# soc.net
KiCad netlist of a schematic drawn in Altium Designer
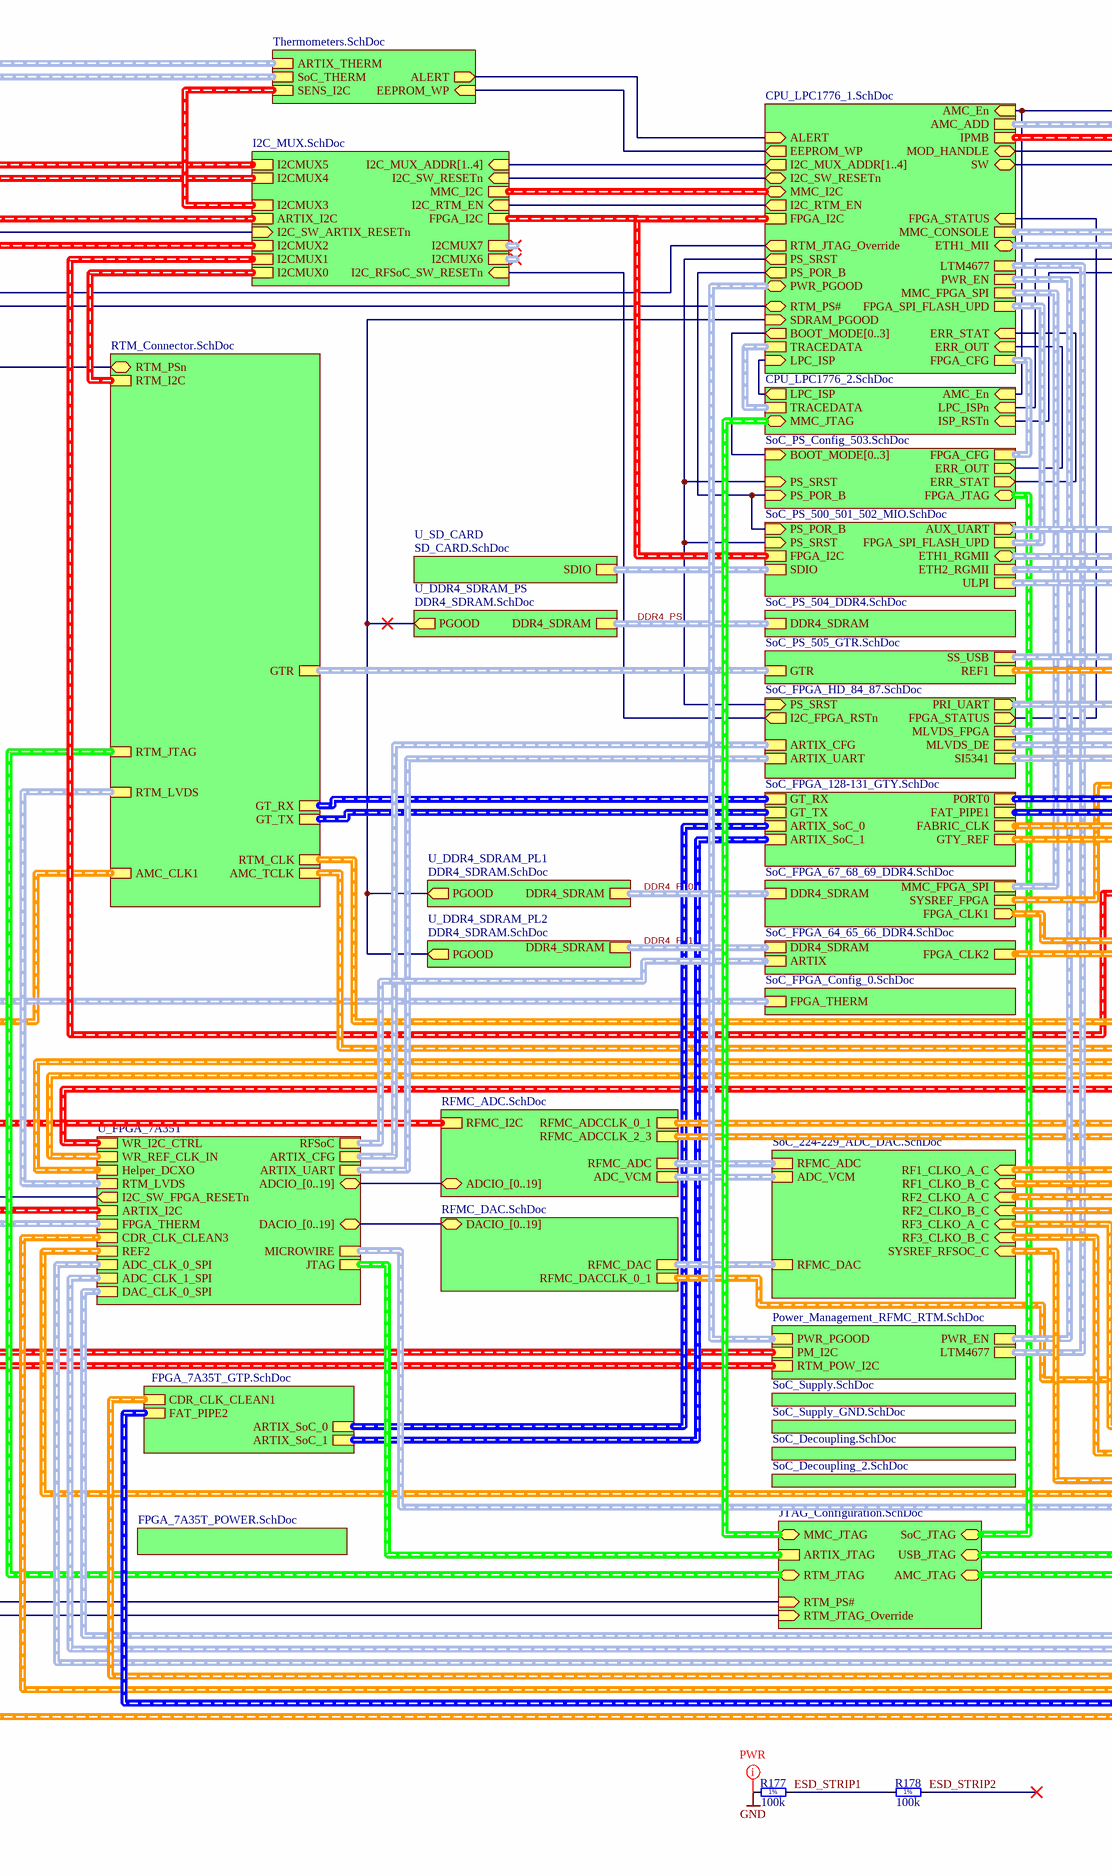
[diagram p0: soc.SchDoc, left]
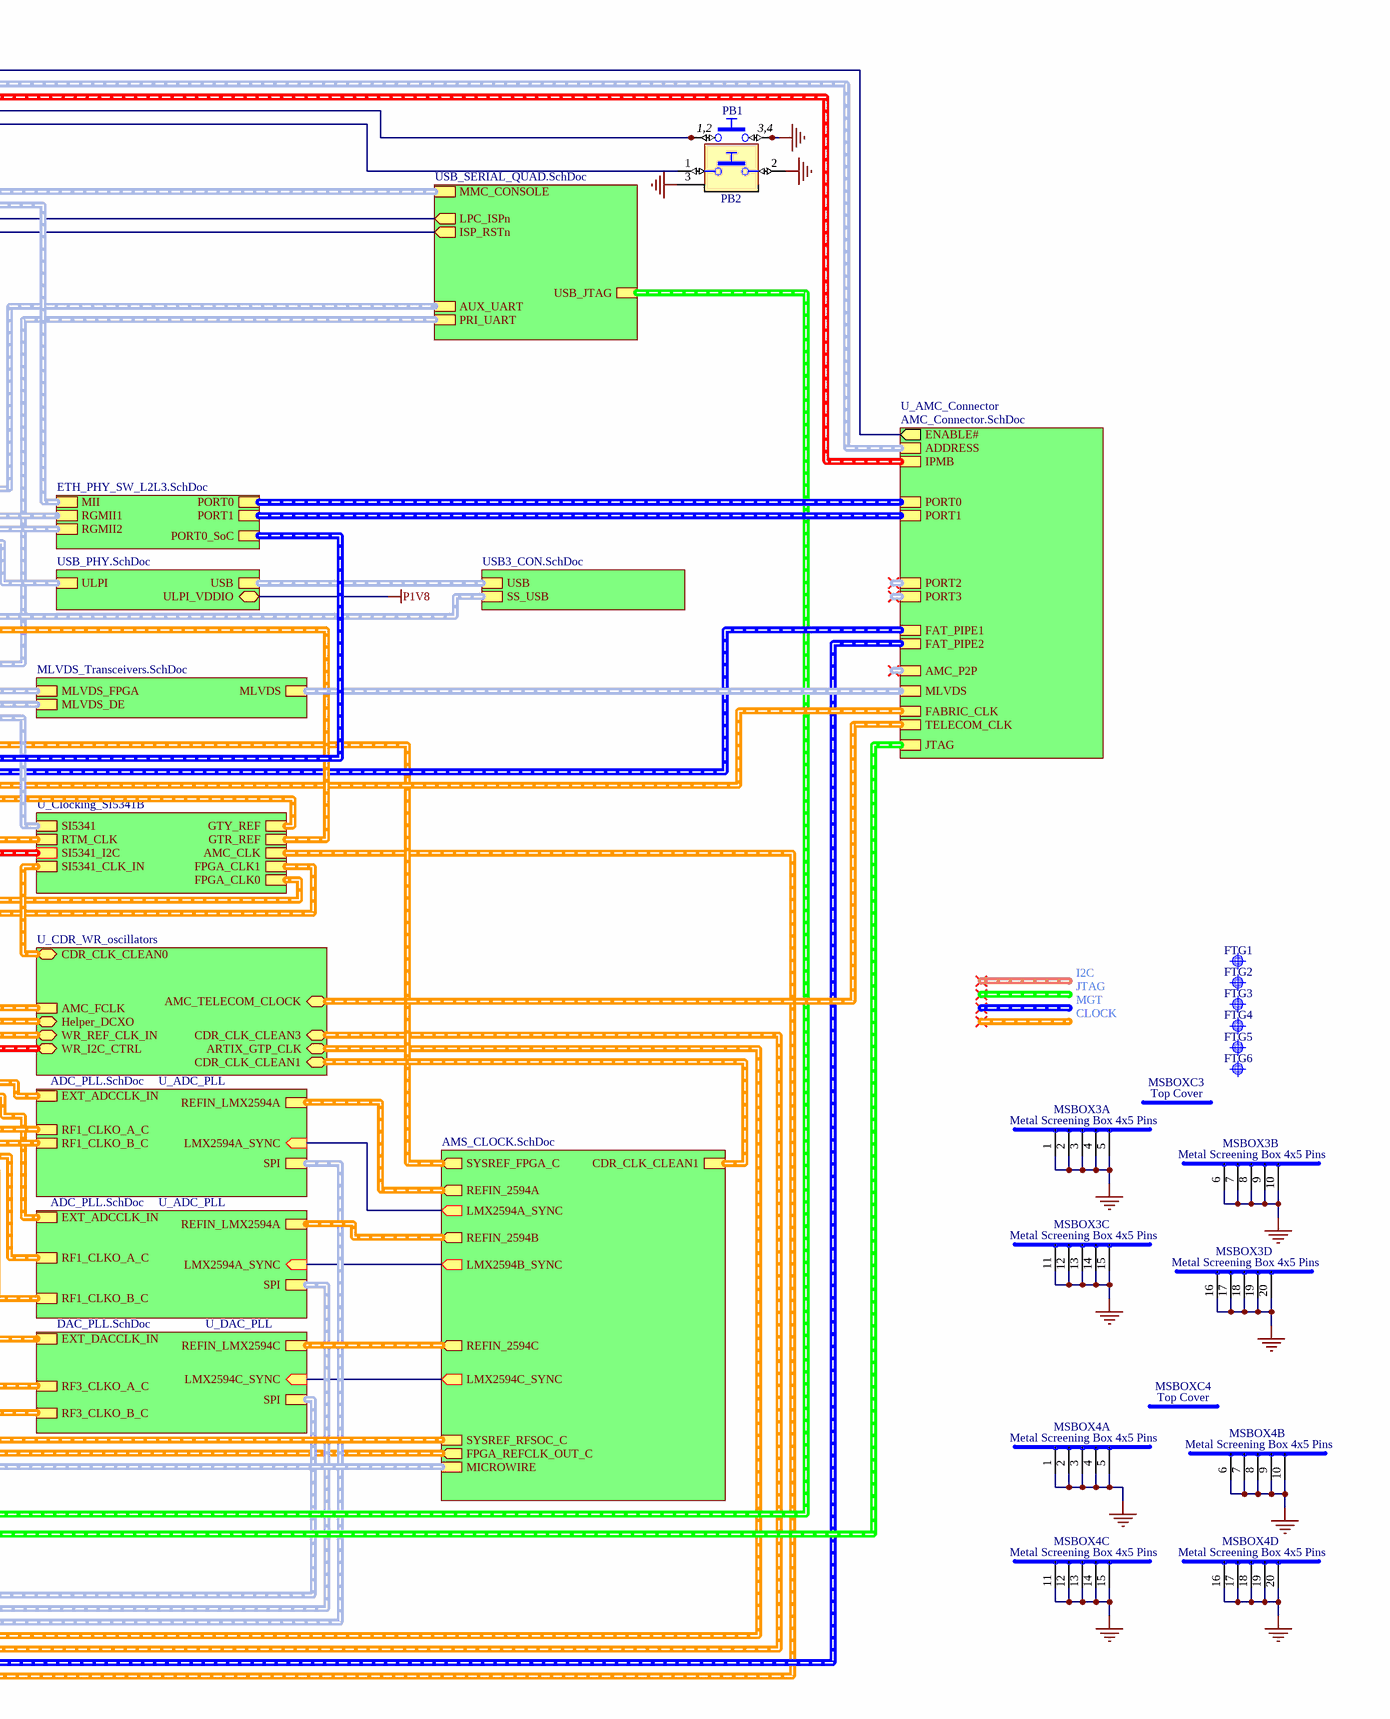
[diagram p1: soc.SchDoc, right]

(export (version "E")
  (design (tool "Eeschema 10.0.6"))
  (components
    (comp (ref "FTG1")
      (value "Use only in PCB")
      (footprint "FIDUCIAL_TOP_C100-200")
      (description "Fiducial Target")
      (fields (field (name "PART NUMBER") "FIDUCIAL_TARGET_C100-200") (field (name "AUTHOR") "CERN DEM JLC"))
      (libsource (lib "Eletro-mechanical") (part "Fiducial Target"))
    )
    (comp (ref "FTG2")
      (value "Use only in PCB")
      (footprint "FIDUCIAL_TOP_C100-200")
      (description "Fiducial Target")
      (fields (field (name "PART NUMBER") "FIDUCIAL_TARGET_C100-200") (field (name "AUTHOR") "CERN DEM JLC"))
      (libsource (lib "Eletro-mechanical") (part "Fiducial Target"))
    )
    (comp (ref "FTG3")
      (value "Use only in PCB")
      (footprint "FIDUCIAL_TOP_S200-400")
      (description "Fiducial Target")
      (fields (field (name "PART NUMBER") "FIDUCIAL_TARGET_S200-400") (field (name "AUTHOR") "CERN DEM JLC"))
      (libsource (lib "Eletro-mechanical") (part "Fiducial Target"))
    )
    (comp (ref "FTG4")
      (value "Use only in PCB")
      (footprint "FIDUCIAL_TOP_C100-200")
      (description "Fiducial Target")
      (fields (field (name "PART NUMBER") "FIDUCIAL_TARGET_C100-200") (field (name "AUTHOR") "CERN DEM JLC"))
      (libsource (lib "Eletro-mechanical") (part "Fiducial Target"))
    )
    (comp (ref "FTG5")
      (value "Use only in PCB")
      (footprint "FIDUCIAL_TOP_C100-200")
      (description "Fiducial Target")
      (fields (field (name "PART NUMBER") "FIDUCIAL_TARGET_C100-200") (field (name "AUTHOR") "CERN DEM JLC"))
      (libsource (lib "Eletro-mechanical") (part "Fiducial Target"))
    )
    (comp (ref "FTG6")
      (value "Use only in PCB")
      (footprint "FIDUCIAL_TOP_S200-400")
      (description "Fiducial Target")
      (fields (field (name "PART NUMBER") "FIDUCIAL_TARGET_S200-400") (field (name "AUTHOR") "CERN DEM JLC"))
      (libsource (lib "Eletro-mechanical") (part "Fiducial Target"))
    )
    (comp (ref "MSBOX3")
      (value "Metal Screening Box 4x5 Pins")
      (footprint "MSBOX_WURTH_36103305")
      (description "Metal Screening Box 20 (4x5) Pins")
      (fields
        (field (name "PART NUMBER") "MSBOX_WURTH_36103305")
        (field (name "MANUFACTURER") "WURTH")
        (field (name "AUTHOR") "CERN DEM JLC")
      )
      (libsource (lib "Eletro-mechanical") (part "Metal Screening Box - 4x5 pins"))
    )
    (comp (ref "MSBOX4")
      (value "Metal Screening Box 4x5 Pins")
      (footprint "MSBOX_WURTH_36103305")
      (description "Metal Screening Box 20 (4x5) Pins")
      (fields
        (field (name "PART NUMBER") "MSBOX_WURTH_36103305")
        (field (name "MANUFACTURER") "WURTH")
        (field (name "AUTHOR") "CERN DEM JLC")
      )
      (libsource (lib "Eletro-mechanical") (part "Metal Screening Box - 4x5 pins"))
    )
    (comp (ref "MSBOXC3")
      (value "Top Cover")
      (footprint "MSBOX_WURTH_36003300")
      (description "Metal Screening Box - Top Cover 0 Pin")
      (fields
        (field (name "PART NUMBER") "MSBOX_WURTH_36003300")
        (field (name "MANUFACTURER") "WURTH")
        (field (name "AUTHOR") "CERN DEM JLC")
      )
      (libsource (lib "Eletro-mechanical") (part "Metal Screening Box - Top Cover"))
    )
    (comp (ref "MSBOXC4")
      (value "Top Cover")
      (footprint "MSBOX_WURTH_36003300")
      (description "Metal Screening Box - Top Cover 0 Pin")
      (fields
        (field (name "PART NUMBER") "MSBOX_WURTH_36003300")
        (field (name "MANUFACTURER") "WURTH")
        (field (name "AUTHOR") "CERN DEM JLC")
      )
      (libsource (lib "Eletro-mechanical") (part "Metal Screening Box - Top Cover"))
    )
    (comp (ref "PB1")
      (value "Push Button")
      (footprint "SW_C&K_HDT0001")
      (description "Push-Button Switch SPDT")
      (fields
        (field (name "MANUFACTURER PART NUMBER") "HDT0001")
        (field (name "MANUFACTURER") "C&K")
        (field (name "AUTHOR") "CERN DEM JLC")
      )
      (libsource (lib "Eletro-mechanical") (part "PB SPST 12NO-34NO"))
    )
    (comp (ref "PB2")
      (value "Push Button")
      (footprint "PB_OMRON_B3U-1100P")
      (description "Push-Button Switch SPDT")
      (fields
        (field (name "PART NUMBER") "PB_OMRON_B3U-1100P")
        (field (name "MANUFACTURER") "OMRON")
        (field (name "AUTHOR") "CERN DEM JLC")
      )
      (libsource (lib "Eletro-mechanical") (part "PB SPST 1NO-2NO 3CASE"))
    )
    (comp (ref "R177")
      (value "100k")
      (footprint "RESC3216X65N")
      (description "Resistor - 1%")
      (fields
        (field (name "PART NUMBER") "R1206_100K_1%_0.25W_100PPM")
        (field (name "POWER") "0.25W")
        (field (name "AUTHOR") "CERN DEM JLC")
      )
      (libsource (lib "Resistors") (part "Resistor - 1%"))
    )
    (comp (ref "R178")
      (value "100k")
      (footprint "RESC3216X65N")
      (description "Resistor - 1%")
      (fields
        (field (name "PART NUMBER") "R1206_100K_1%_0.25W_100PPM")
        (field (name "POWER") "0.25W")
        (field (name "AUTHOR") "CERN DEM JLC")
      )
      (libsource (lib "Resistors") (part "Resistor - 1%"))
    )
  )
  (nets
    (net (code "35") (name "/ESD_STRIP1") (class "Default")
      (node (ref "R177") (pin "2") (pinfunction "2_2") (pintype "passive"))
      (node (ref "R178") (pin "1") (pinfunction "1_1") (pintype "passive"))
    )
    (net (code "36") (name "/ESD_STRIP2") (class "Default")
      (node (ref "R178") (pin "2") (pinfunction "2_2") (pintype "passive+no_connect"))
    )
    (net (code "90") (name "/MOD_HANDLE") (class "Default")
      (node (ref "PB1") (pin "1") (pinfunction "1_1") (pintype "bidirectional"))
      (node (ref "PB1") (pin "2") (pinfunction "2_2") (pintype "bidirectional"))
    )
    (net (code "121") (name "/SW") (class "Default")
      (node (ref "PB2") (pin "1") (pinfunction "1_1") (pintype "bidirectional"))
    )
    (net (code "133") (name "GND") (class "Default")
      (node (ref "MSBOX3") (pin "1") (pinfunction "1_1") (pintype "passive"))
      (node (ref "MSBOX3") (pin "10") (pinfunction "10_10") (pintype "passive"))
      (node (ref "MSBOX3") (pin "11") (pinfunction "11_11") (pintype "passive"))
      (node (ref "MSBOX3") (pin "12") (pinfunction "12_12") (pintype "passive"))
      (node (ref "MSBOX3") (pin "13") (pinfunction "13_13") (pintype "passive"))
      (node (ref "MSBOX3") (pin "14") (pinfunction "14_14") (pintype "passive"))
      (node (ref "MSBOX3") (pin "15") (pinfunction "15_15") (pintype "passive"))
      (node (ref "MSBOX3") (pin "16") (pinfunction "16_16") (pintype "passive"))
      (node (ref "MSBOX3") (pin "17") (pinfunction "17_17") (pintype "passive"))
      (node (ref "MSBOX3") (pin "18") (pinfunction "18_18") (pintype "passive"))
      (node (ref "MSBOX3") (pin "19") (pinfunction "19_19") (pintype "passive"))
      (node (ref "MSBOX3") (pin "2") (pinfunction "2_2") (pintype "passive"))
      (node (ref "MSBOX3") (pin "20") (pinfunction "20_20") (pintype "passive"))
      (node (ref "MSBOX3") (pin "3") (pinfunction "3_3") (pintype "passive"))
      (node (ref "MSBOX3") (pin "4") (pinfunction "4_4") (pintype "passive"))
      (node (ref "MSBOX3") (pin "5") (pinfunction "5_5") (pintype "passive"))
      (node (ref "MSBOX3") (pin "6") (pinfunction "6_6") (pintype "passive"))
      (node (ref "MSBOX3") (pin "7") (pinfunction "7_7") (pintype "passive"))
      (node (ref "MSBOX3") (pin "8") (pinfunction "8_8") (pintype "passive"))
      (node (ref "MSBOX3") (pin "9") (pinfunction "9_9") (pintype "passive"))
      (node (ref "MSBOX4") (pin "1") (pinfunction "1_1") (pintype "passive"))
      (node (ref "MSBOX4") (pin "10") (pinfunction "10_10") (pintype "passive"))
      (node (ref "MSBOX4") (pin "11") (pinfunction "11_11") (pintype "passive"))
      (node (ref "MSBOX4") (pin "12") (pinfunction "12_12") (pintype "passive"))
      (node (ref "MSBOX4") (pin "13") (pinfunction "13_13") (pintype "passive"))
      (node (ref "MSBOX4") (pin "14") (pinfunction "14_14") (pintype "passive"))
      (node (ref "MSBOX4") (pin "15") (pinfunction "15_15") (pintype "passive"))
      (node (ref "MSBOX4") (pin "16") (pinfunction "16_16") (pintype "passive"))
      (node (ref "MSBOX4") (pin "17") (pinfunction "17_17") (pintype "passive"))
      (node (ref "MSBOX4") (pin "18") (pinfunction "18_18") (pintype "passive"))
      (node (ref "MSBOX4") (pin "19") (pinfunction "19_19") (pintype "passive"))
      (node (ref "MSBOX4") (pin "2") (pinfunction "2_2") (pintype "passive"))
      (node (ref "MSBOX4") (pin "20") (pinfunction "20_20") (pintype "passive"))
      (node (ref "MSBOX4") (pin "3") (pinfunction "3_3") (pintype "passive"))
      (node (ref "MSBOX4") (pin "4") (pinfunction "4_4") (pintype "passive"))
      (node (ref "MSBOX4") (pin "5") (pinfunction "5_5") (pintype "passive"))
      (node (ref "MSBOX4") (pin "6") (pinfunction "6_6") (pintype "passive"))
      (node (ref "MSBOX4") (pin "7") (pinfunction "7_7") (pintype "passive"))
      (node (ref "MSBOX4") (pin "8") (pinfunction "8_8") (pintype "passive"))
      (node (ref "MSBOX4") (pin "9") (pinfunction "9_9") (pintype "passive"))
      (node (ref "PB1") (pin "3") (pinfunction "3_3") (pintype "bidirectional"))
      (node (ref "PB1") (pin "4") (pinfunction "4_4") (pintype "bidirectional"))
      (node (ref "PB2") (pin "2") (pinfunction "2_2") (pintype "bidirectional"))
      (node (ref "PB2") (pin "3") (pinfunction "3_3") (pintype "passive"))
      (node (ref "R177") (pin "1") (pinfunction "1_1") (pintype "passive"))
    )
  )
)
